# DELA-EPROMMER_II_27512_Extension_Rev1.net
KiCad netlist of a schematic drawn in EAGLE
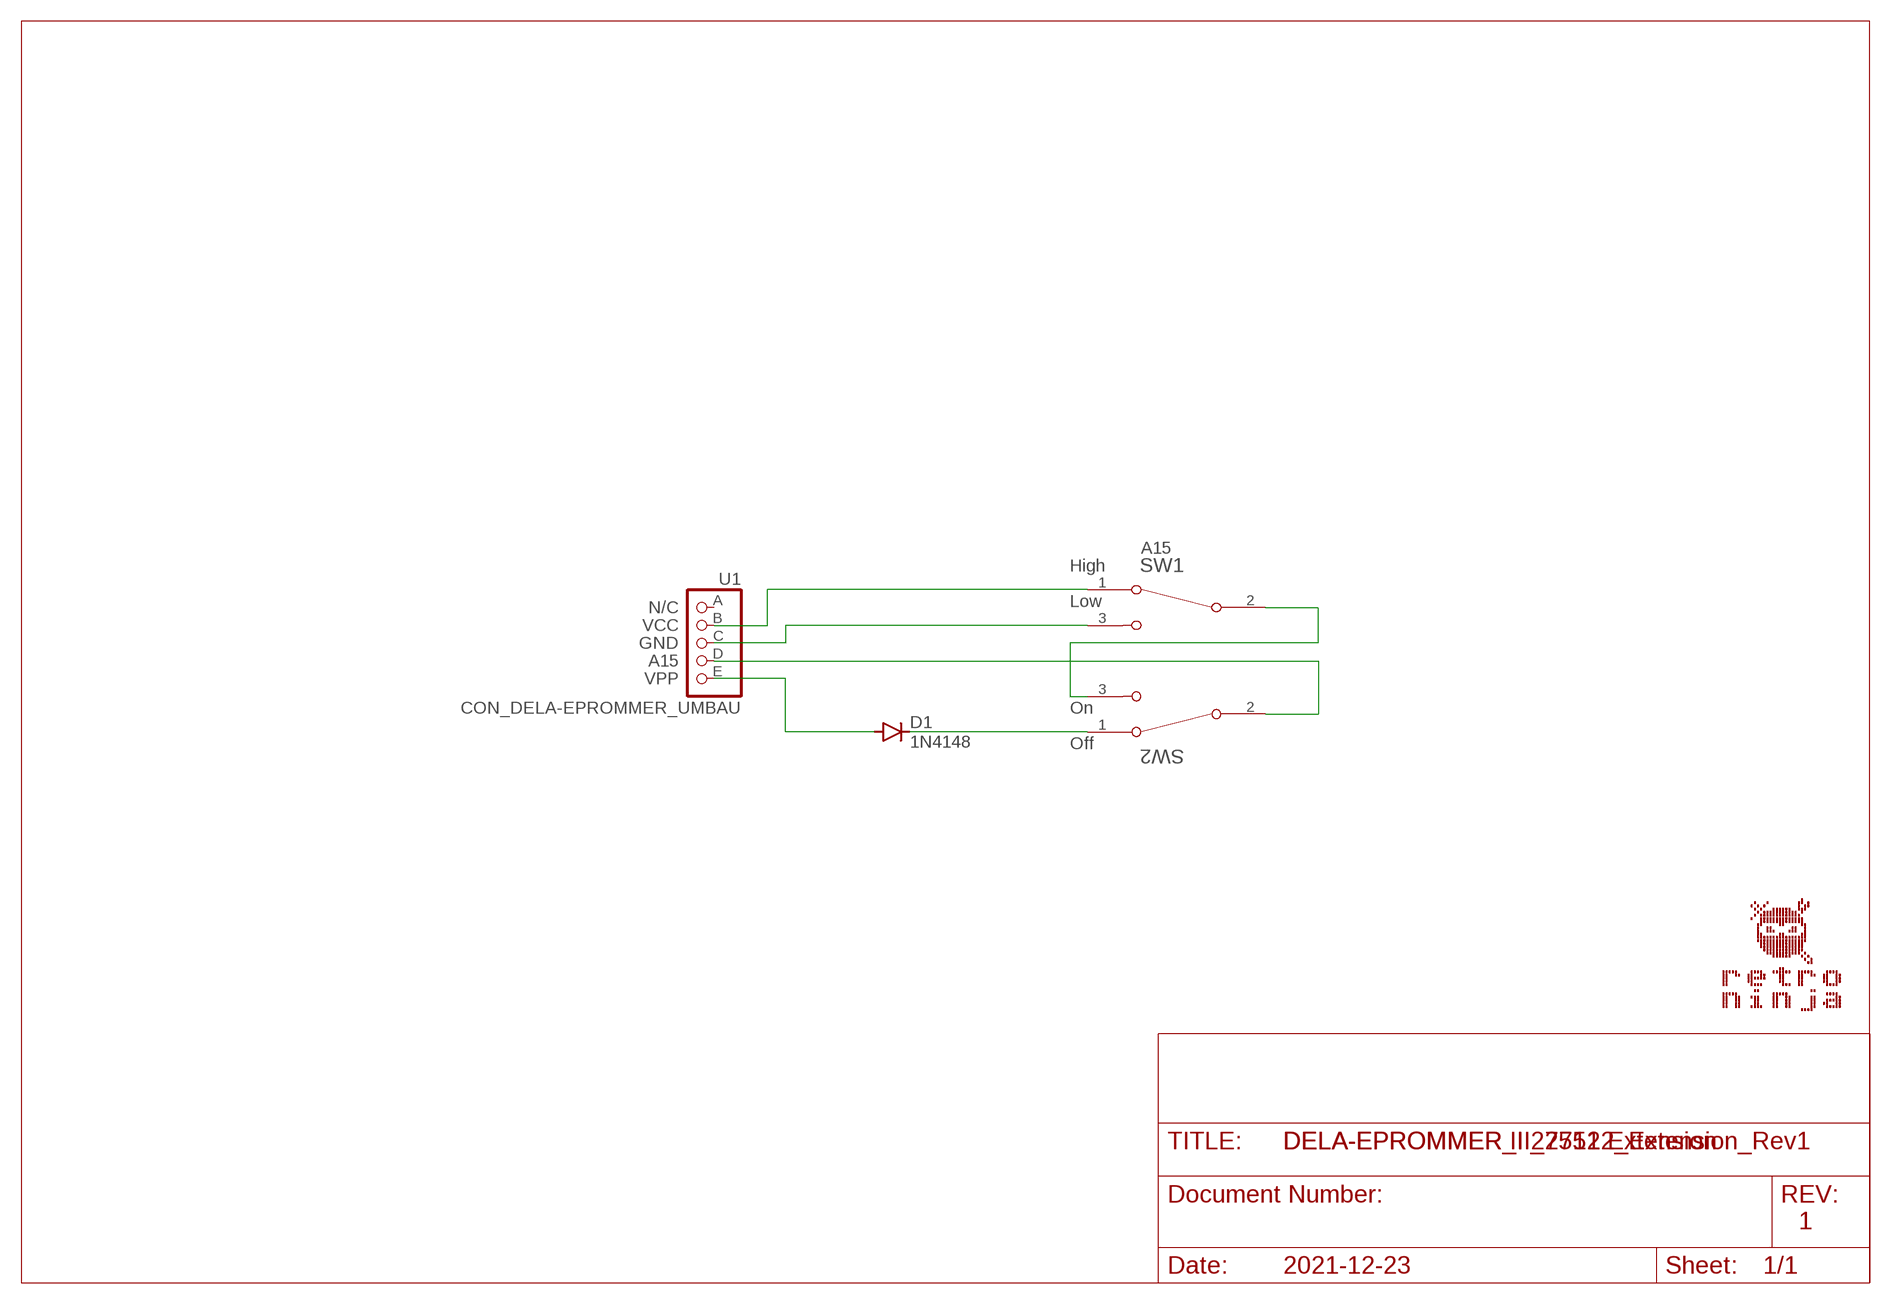
[diagram p0: schematic, sheet 1]

(export (version "E")
  (design (tool "Eeschema 10.0.6"))
  (components
    (comp (ref "D1")
      (value "1N4148")
      (footprint "eagle-import:DO35-10")
      (libsource (lib "eagle-import") (part "DIODE_DO35-10"))
    )
    (comp (ref "SW1")
      (value "SWITCH_SLIDE_2POS_2MM")
      (footprint "eagle-import:SWITCH_SLIDE_2POS_2MM")
      (libsource (lib "eagle-import") (part "SWITCH_SLIDE_2POS_2MM"))
    )
    (comp (ref "SW2")
      (value "SWITCH_SLIDE_2POS_2MM")
      (footprint "eagle-import:SWITCH_SLIDE_2POS_2MM")
      (libsource (lib "eagle-import") (part "SWITCH_SLIDE_2POS_2MM"))
    )
    (comp (ref "U1")
      (value "CON_DELA-EPROMMER_UMBAU")
      (footprint "eagle-import:CON_DELA-EPROMMER_UMBAU")
      (libsource (lib "eagle-import") (part "CON_DELA-EPROMMER_UMBAU"))
    )
  )
  (nets
    (net (code "1") (name "Net-(D1-PadA)") (class "Default")
      (node (ref "D1") (pin "A") (pinfunction "A_A") (pintype "passive"))
      (node (ref "U1") (pin "E") (pinfunction "E_E") (pintype "passive"))
    )
    (net (code "2") (name "Net-(D1-PadC)") (class "Default")
      (node (ref "D1") (pin "C") (pinfunction "C_C") (pintype "passive"))
      (node (ref "SW2") (pin "1") (pinfunction "1_1") (pintype "passive"))
    )
    (net (code "3") (name "Net-(SW1-Pad1)") (class "Default")
      (node (ref "SW1") (pin "1") (pinfunction "1_1") (pintype "passive"))
      (node (ref "U1") (pin "B") (pinfunction "B_B") (pintype "passive"))
    )
    (net (code "4") (name "Net-(SW1-Pad2)") (class "Default")
      (node (ref "SW1") (pin "2") (pinfunction "2_2") (pintype "passive"))
      (node (ref "SW2") (pin "3") (pinfunction "3_3") (pintype "passive"))
    )
    (net (code "5") (name "Net-(SW1-Pad3)") (class "Default")
      (node (ref "SW1") (pin "3") (pinfunction "3_3") (pintype "passive"))
      (node (ref "U1") (pin "C") (pinfunction "C_C") (pintype "passive"))
    )
    (net (code "6") (name "Net-(SW2-Pad2)") (class "Default")
      (node (ref "SW2") (pin "2") (pinfunction "2_2") (pintype "passive"))
      (node (ref "U1") (pin "D") (pinfunction "D_D") (pintype "passive"))
    )
    (net (code "7") (name "unconnected-(U1-PadA)") (class "Default")
      (node (ref "U1") (pin "A") (pinfunction "A_A") (pintype "passive"))
    )
  )
)
